# MainBoard_V1p0_PER.net
KiCad netlist of a schematic drawn in Altium Designer
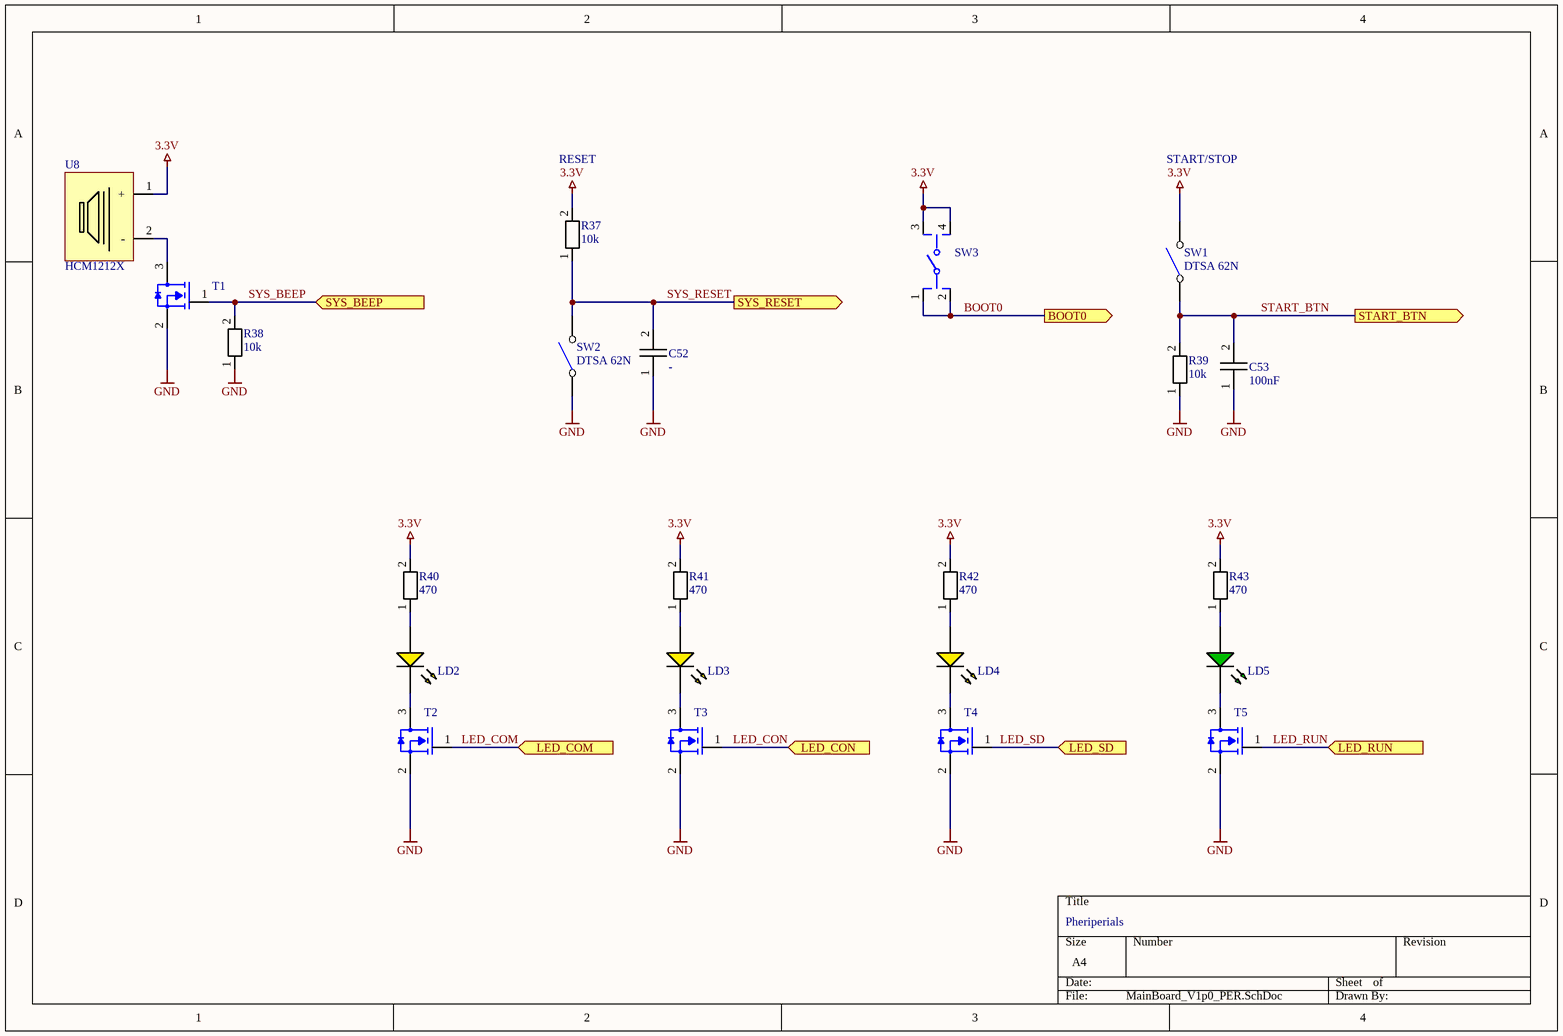
[diagram p0: MainBoard_V1p0_PER.SchDoc]

(export (version "E")
  (design (tool "Eeschema 10.0.6"))
  (components
    (comp (ref "C52") (value "-") (footprint "0805_C") (libsource (lib "Schlib1") (part "CAPACITOR")))
    (comp (ref "C53") (value "100nF") (footprint "0805_C") (libsource (lib "Schlib1") (part "CAPACITOR")))
    (comp (ref "LD2")
      (value "LED_YEL")
      (footprint "LED_SMD_90DEG_YEL")
      (libsource (lib "Schlib1") (part "LED_YEL"))
    )
    (comp (ref "LD3")
      (value "LED_YEL")
      (footprint "LED_SMD_90DEG_YEL")
      (libsource (lib "Schlib1") (part "LED_YEL"))
    )
    (comp (ref "LD4")
      (value "LED_YEL")
      (footprint "LED_SMD_90DEG_YEL")
      (libsource (lib "Schlib1") (part "LED_YEL"))
    )
    (comp (ref "LD5")
      (value "LED_GREEN")
      (footprint "LED_SMD_90DEG_GRE")
      (libsource (lib "Schlib1") (part "LED_GREEN"))
    )
    (comp (ref "R37") (value "10k") (footprint "0805") (libsource (lib "Schlib1") (part "RESISTOR")))
    (comp (ref "R38") (value "10k") (footprint "0805") (libsource (lib "Schlib1") (part "RESISTOR")))
    (comp (ref "R39") (value "10k") (footprint "0805") (libsource (lib "Schlib1") (part "RESISTOR")))
    (comp (ref "R40") (value "470") (footprint "0805") (libsource (lib "Schlib1") (part "RESISTOR")))
    (comp (ref "R41") (value "470") (footprint "0805") (libsource (lib "Schlib1") (part "RESISTOR")))
    (comp (ref "R42") (value "470") (footprint "0805") (libsource (lib "Schlib1") (part "RESISTOR")))
    (comp (ref "R43") (value "470") (footprint "0805") (libsource (lib "Schlib1") (part "RESISTOR")))
    (comp (ref "SW1")
      (value "DTSA 62N")
      (footprint "SW_DTSA-62N")
      (libsource (lib "Schlib1") (part "SW_DTSA 62N"))
    )
    (comp (ref "SW2")
      (value "DTSA 62N")
      (footprint "SW_DTSA-62N")
      (libsource (lib "Schlib1") (part "SW_DTSA 62N"))
    )
    (comp (ref "SW3")
      (value "Switch_C&K_KSC241JLFS_eec")
      (footprint "C&K_KSC241JLFS")
      (description "SWITCH TACTILE SPST-NO 0.05A 32V")
      (fields (field (name "PART NUMBER") "KSC241JLFS") (field (name "MANUFACTURER") "C&K"))
      (libsource (lib "Schlib1") (part "Switch_C&K_KSC241JLFS_eec"))
    )
    (comp (ref "T1")
      (value "MMBF170")
      (footprint "SOT23")
      (description "N MOSFET")
      (libsource (lib "Schlib1") (part "MMBF170"))
    )
    (comp (ref "T2")
      (value "MMBF170")
      (footprint "SOT23")
      (description "N MOSFET")
      (libsource (lib "Schlib1") (part "MMBF170"))
    )
    (comp (ref "T3")
      (value "MMBF170")
      (footprint "SOT23")
      (description "N MOSFET")
      (libsource (lib "Schlib1") (part "MMBF170"))
    )
    (comp (ref "T4")
      (value "MMBF170")
      (footprint "SOT23")
      (description "N MOSFET")
      (libsource (lib "Schlib1") (part "MMBF170"))
    )
    (comp (ref "T5")
      (value "MMBF170")
      (footprint "SOT23")
      (description "N MOSFET")
      (libsource (lib "Schlib1") (part "MMBF170"))
    )
    (comp (ref "U8") (value "HCM1212X") (footprint "HCM1212X") (libsource (lib "Schlib1") (part "HCM1212X")))
  )
  (nets
    (net (code "1") (name "/BOOT0") (class "Default")
      (node (ref "SW3") (pin "1") (pinfunction "1_1") (pintype "passive"))
      (node (ref "SW3") (pin "2") (pinfunction "2_2") (pintype "passive"))
    )
    (net (code "2") (name "/LED_COM") (class "Default")
      (node (ref "T2") (pin "1") (pinfunction "Gate_1") (pintype "passive"))
    )
    (net (code "3") (name "/LED_CON") (class "Default")
      (node (ref "T3") (pin "1") (pinfunction "Gate_1") (pintype "passive"))
    )
    (net (code "4") (name "/LED_RUN") (class "Default")
      (node (ref "T5") (pin "1") (pinfunction "Gate_1") (pintype "passive"))
    )
    (net (code "5") (name "/LED_SD") (class "Default")
      (node (ref "T4") (pin "1") (pinfunction "Gate_1") (pintype "passive"))
    )
    (net (code "6") (name "/START_BTN") (class "Default")
      (node (ref "C53") (pin "2") (pinfunction "2_2") (pintype "passive"))
      (node (ref "R39") (pin "2") (pinfunction "1_2") (pintype "passive"))
      (node (ref "SW1") (pin "1") (pinfunction "1_1") (pintype "passive"))
    )
    (net (code "7") (name "/SYS_BEEP") (class "Default")
      (node (ref "R38") (pin "2") (pinfunction "1_2") (pintype "passive"))
      (node (ref "T1") (pin "1") (pinfunction "Gate_1") (pintype "passive"))
    )
    (net (code "8") (name "/SYS_RESET") (class "Default")
      (node (ref "C52") (pin "2") (pinfunction "2_2") (pintype "passive"))
      (node (ref "R37") (pin "1") (pinfunction "0_1") (pintype "passive"))
      (node (ref "SW2") (pin "2") (pinfunction "2_2") (pintype "passive"))
    )
    (net (code "9") (name "3.3V") (class "Default")
      (node (ref "R37") (pin "2") (pinfunction "1_2") (pintype "passive"))
      (node (ref "R40") (pin "2") (pinfunction "1_2") (pintype "passive"))
      (node (ref "R41") (pin "2") (pinfunction "1_2") (pintype "passive"))
      (node (ref "R42") (pin "2") (pinfunction "1_2") (pintype "passive"))
      (node (ref "R43") (pin "2") (pinfunction "1_2") (pintype "passive"))
      (node (ref "SW1") (pin "2") (pinfunction "2_2") (pintype "passive"))
      (node (ref "SW3") (pin "3") (pinfunction "3_3") (pintype "passive"))
      (node (ref "SW3") (pin "4") (pinfunction "4_4") (pintype "passive"))
      (node (ref "U8") (pin "1") (pinfunction "+_1") (pintype "passive"))
    )
    (net (code "10") (name "GND") (class "Default")
      (node (ref "C52") (pin "1") (pinfunction "1_1") (pintype "passive"))
      (node (ref "C53") (pin "1") (pinfunction "1_1") (pintype "passive"))
      (node (ref "R38") (pin "1") (pinfunction "0_1") (pintype "passive"))
      (node (ref "R39") (pin "1") (pinfunction "0_1") (pintype "passive"))
      (node (ref "SW2") (pin "1") (pinfunction "1_1") (pintype "passive"))
      (node (ref "T1") (pin "2") (pinfunction "Source_2") (pintype "passive"))
      (node (ref "T2") (pin "2") (pinfunction "Source_2") (pintype "passive"))
      (node (ref "T3") (pin "2") (pinfunction "Source_2") (pintype "passive"))
      (node (ref "T4") (pin "2") (pinfunction "Source_2") (pintype "passive"))
      (node (ref "T5") (pin "2") (pinfunction "Source_2") (pintype "passive"))
    )
    (net (code "11") (name "Net-(R40-0)") (class "Default")
      (node (ref "LD2") (pin "A") (pinfunction "A_A") (pintype "passive"))
      (node (ref "R40") (pin "1") (pinfunction "0_1") (pintype "passive"))
    )
    (net (code "12") (name "Net-(R41-0)") (class "Default")
      (node (ref "LD3") (pin "A") (pinfunction "A_A") (pintype "passive"))
      (node (ref "R41") (pin "1") (pinfunction "0_1") (pintype "passive"))
    )
    (net (code "13") (name "Net-(R42-0)") (class "Default")
      (node (ref "LD4") (pin "A") (pinfunction "A_A") (pintype "passive"))
      (node (ref "R42") (pin "1") (pinfunction "0_1") (pintype "passive"))
    )
    (net (code "14") (name "Net-(R43-0)") (class "Default")
      (node (ref "LD5") (pin "A") (pinfunction "A_A") (pintype "passive"))
      (node (ref "R43") (pin "1") (pinfunction "0_1") (pintype "passive"))
    )
    (net (code "15") (name "Net-(T1-Drain)") (class "Default")
      (node (ref "T1") (pin "3") (pinfunction "Drain_3") (pintype "passive"))
      (node (ref "U8") (pin "2") (pinfunction "-_2") (pintype "passive"))
    )
    (net (code "16") (name "Net-(T2-Drain)") (class "Default")
      (node (ref "LD2") (pin "K") (pinfunction "K_K") (pintype "passive"))
      (node (ref "T2") (pin "3") (pinfunction "Drain_3") (pintype "passive"))
    )
    (net (code "17") (name "Net-(T3-Drain)") (class "Default")
      (node (ref "LD3") (pin "K") (pinfunction "K_K") (pintype "passive"))
      (node (ref "T3") (pin "3") (pinfunction "Drain_3") (pintype "passive"))
    )
    (net (code "18") (name "Net-(T4-Drain)") (class "Default")
      (node (ref "LD4") (pin "K") (pinfunction "K_K") (pintype "passive"))
      (node (ref "T4") (pin "3") (pinfunction "Drain_3") (pintype "passive"))
    )
    (net (code "19") (name "Net-(T5-Drain)") (class "Default")
      (node (ref "LD5") (pin "K") (pinfunction "K_K") (pintype "passive"))
      (node (ref "T5") (pin "3") (pinfunction "Drain_3") (pintype "passive"))
    )
  )
)
